# battery_and_current_sense.net
KiCad netlist of a schematic drawn in Altium Designer
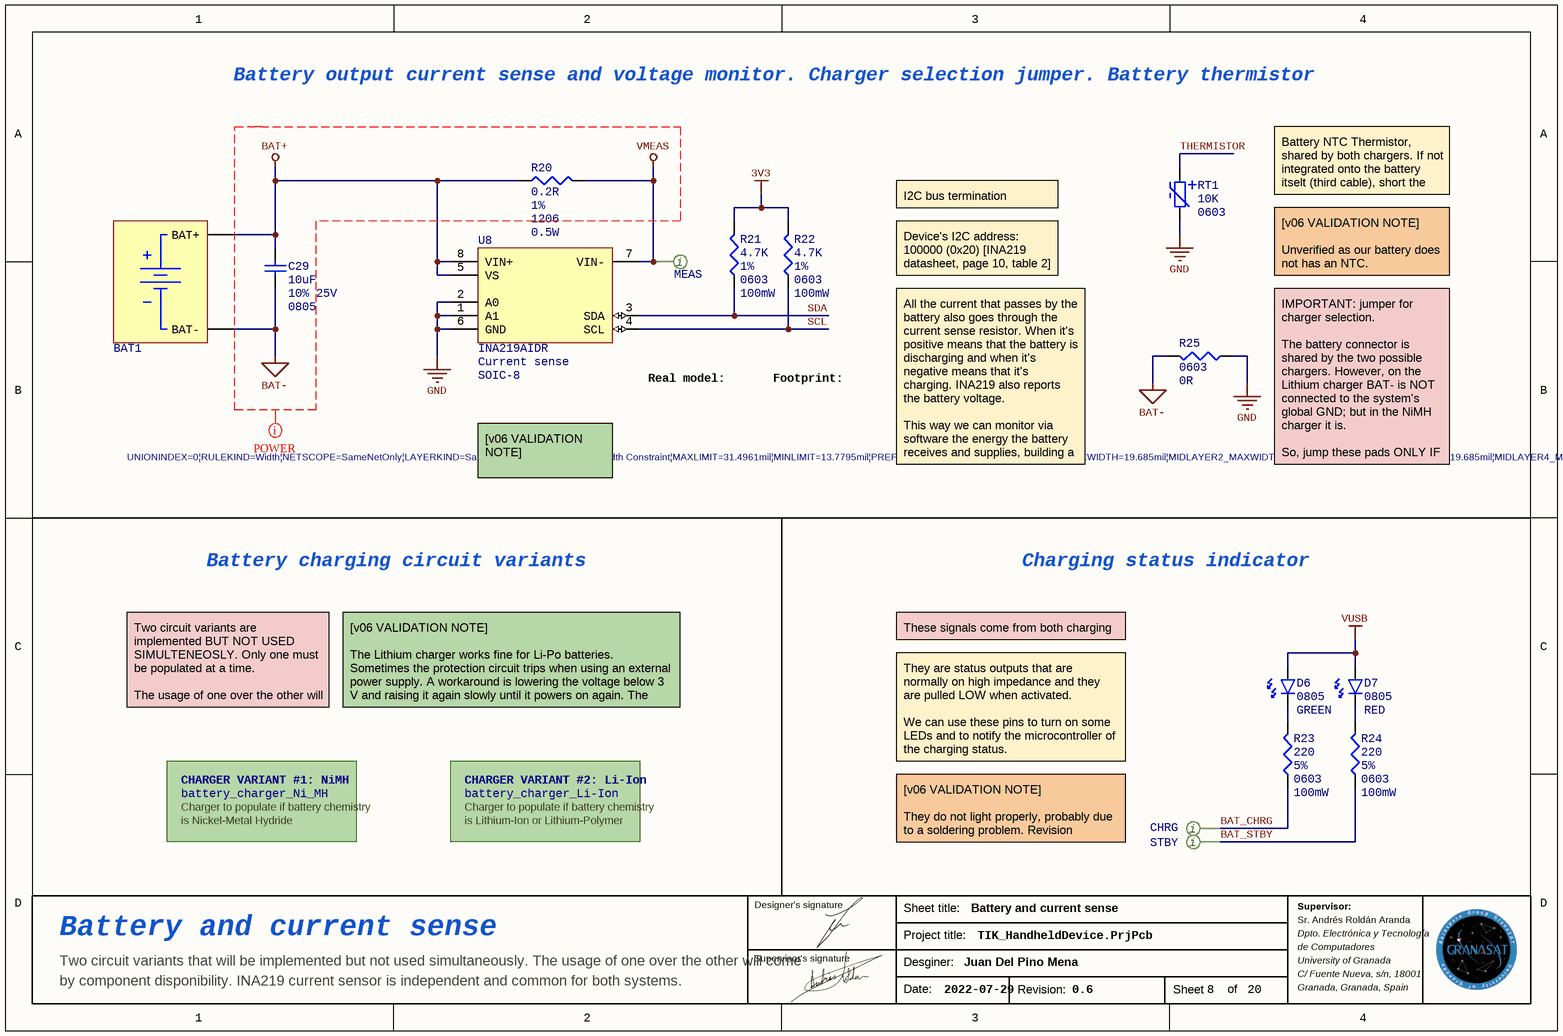
[diagram p0: battery_and_current_sense.SchDoc]

(export (version "E")
  (design (tool "Eeschema 10.0.6"))
  (components
    (comp (ref "BAT1")
      (value "Battery pads")
      (footprint "BATTERY_PADS")
      (description "Generic 2-Pad battery connector")
      (libsource (lib "tik_handheld_schlib") (part "Battery pads"))
    )
    (comp (ref "C29")
      (value "10uF")
      (footprint "CAP 0805_2012")
      (description "Ceramic cap size 0805")
      (fields
        (field (name "TOLERANCE") "10% 25V")
        (field (name "PACKAGEDESCRIPTION") "0805")
        (field (name "Comment") "Cap_cer_0805")
      )
      (libsource (lib "tik_handheld_schlib") (part "Cap_cer_0805_10uF_10%"))
    )
    (comp (ref "CHRG")
      (value "Test Point Pad dual sided")
      (footprint "TEST POINT PAD")
      (description "Test point - PCB Pad dual sided")
      (libsource (lib "tik_handheld_schlib") (part "Test Point Pad dual sided"))
    )
    (comp (ref "D6")
      (value "Diode LED_G_0805")
      (footprint "LED 0805_2012 GREEN")
      (description "Low power LED color Green")
      (fields (field (name "PACKAGEDESCRIPTION") "0805") (field (name "TYPE") "GREEN"))
      (libsource (lib "tik_handheld_schlib") (part "Diode LED_G_0805"))
    )
    (comp (ref "D7")
      (value "Diode LED_R_0805")
      (footprint "LED 0805_2012 RED")
      (description "Low power LED color Red")
      (fields (field (name "PACKAGEDESCRIPTION") "0805") (field (name "TYPE") "RED"))
      (libsource (lib "tik_handheld_schlib") (part "Diode LED_R_0805"))
    )
    (comp (ref "MEAS")
      (value "Test Point Pad dual sided")
      (footprint "TEST POINT PAD")
      (description "Test point - PCB Pad dual sided")
      (libsource (lib "tik_handheld_schlib") (part "Test Point Pad dual sided"))
    )
    (comp (ref "R20")
      (value "0.2R")
      (footprint "RES 1206_3216")
      (description "Res size 1206 SMD mounting, high power, shunt, current sense.")
      (fields
        (field (name "TOLERANCE") "1%")
        (field (name "PACKAGEDESCRIPTION") "1206")
        (field (name "POWERDISIPATED") "0.5W")
        (field (name "Comment") "sense")
      )
      (libsource (lib "tik_handheld_schlib") (part "Res_1206_0R2_1%_500mW"))
    )
    (comp (ref "R21")
      (value "4.7K")
      (footprint "RES 0603_1608")
      (description "Res size 0603 SMD mounting, low power")
      (fields
        (field (name "TOLERANCE") "1%")
        (field (name "PACKAGEDESCRIPTION") "0603")
        (field (name "POWERDISIPATED") "100mW")
        (field (name "Comment") "Res_0603_4.7K_1%_100mW")
      )
      (libsource (lib "tik_handheld_schlib") (part "Res_0603_4.7K_1%_100mW"))
    )
    (comp (ref "R22")
      (value "4.7K")
      (footprint "RES 0603_1608")
      (description "Res size 0603 SMD mounting, low power")
      (fields
        (field (name "TOLERANCE") "1%")
        (field (name "PACKAGEDESCRIPTION") "0603")
        (field (name "POWERDISIPATED") "100mW")
        (field (name "Comment") "Res_0603_4.7K_1%_100mW")
      )
      (libsource (lib "tik_handheld_schlib") (part "Res_0603_4.7K_1%_100mW"))
    )
    (comp (ref "R23")
      (value "220")
      (footprint "RES 0603_1608")
      (description "Res size 0603 SMD mounting, low power")
      (fields
        (field (name "TOLERANCE") "5%")
        (field (name "PACKAGEDESCRIPTION") "0603")
        (field (name "POWERDISIPATED") "100mW")
        (field (name "Comment") "Res_0603_220_5%_100mW")
      )
      (libsource (lib "tik_handheld_schlib") (part "Res_0603_220_5%_100mW"))
    )
    (comp (ref "R24")
      (value "220")
      (footprint "RES 0603_1608")
      (description "Res size 0603 SMD mounting, low power")
      (fields
        (field (name "TOLERANCE") "5%")
        (field (name "PACKAGEDESCRIPTION") "0603")
        (field (name "POWERDISIPATED") "100mW")
        (field (name "Comment") "Res_0603_220_5%_100mW")
      )
      (libsource (lib "tik_handheld_schlib") (part "Res_0603_220_5%_100mW"))
    )
    (comp (ref "R25")
      (value "0R")
      (footprint "RES 0603_1608")
      (description "Res size 0603 SMD mounting, zero-ohm 0R Yageo RC0603JR-070RL")
      (fields
        (field (name "TOLERANCE") "5%")
        (field (name "PACKAGEDESCRIPTION") "0603")
        (field (name "Comment") "Res_0603_0ohm")
      )
      (libsource (lib "tik_handheld_schlib") (part "Res_0603_0ohm"))
    )
    (comp (ref "RT1")
      (value "10K")
      (footprint "NTC THT ver")
      (description "NTC THERMISTOR 10K for solding a cable from the battery NTC")
      (fields (field (name "PACKAGEDESCRIPTION") "0603") (field (name "Comment") "NTC 10K tht"))
      (libsource (lib "tik_handheld_schlib") (part "NTC 10K tht"))
    )
    (comp (ref "STBY")
      (value "Test Point Pad dual sided")
      (footprint "TEST POINT PAD")
      (description "Test point - PCB Pad dual sided")
      (libsource (lib "tik_handheld_schlib") (part "Test Point Pad dual sided"))
    )
    (comp (ref "U8")
      (value "INA219")
      (footprint "SOIC-8-D0008A INA219D")
      (description "Zero-Drift, Bi-Directional CURRENT/POWER MONITOR with I2C. SOIC-8 (D) Package")
      (fields
        (field (name "PART") "INA219AIDR")
        (field (name "TYPE") "Current sense")
        (field (name "PACKAGEDESCRIPTION") "SOIC-8")
      )
      (libsource (lib "tik_handheld_schlib") (part "IC INA219 current sense"))
    )
  )
  (nets
    (net (code "1") (name "/BAT_CHRG") (class "Default")
      (node (ref "CHRG") (pin "1") (pinfunction "1_1") (pintype "passive"))
      (node (ref "R23") (pin "1") (pinfunction "1_1") (pintype "passive"))
    )
    (net (code "2") (name "/BAT_STBY") (class "Default")
      (node (ref "R24") (pin "1") (pinfunction "1_1") (pintype "passive"))
      (node (ref "STBY") (pin "1") (pinfunction "1_1") (pintype "passive"))
    )
    (net (code "3") (name "/SCL") (class "Default")
      (node (ref "R22") (pin "1") (pinfunction "1_1") (pintype "passive"))
      (node (ref "U8") (pin "4") (pinfunction "SCL_4") (pintype "bidirectional"))
    )
    (net (code "4") (name "/SDA") (class "Default")
      (node (ref "R21") (pin "1") (pinfunction "1_1") (pintype "passive"))
      (node (ref "U8") (pin "3") (pinfunction "SDA_3") (pintype "bidirectional"))
    )
    (net (code "5") (name "/THERMISTOR") (class "Default")
      (node (ref "RT1") (pin "1") (pinfunction "1_1") (pintype "passive"))
    )
    (net (code "6") (name "3V3") (class "Default")
      (node (ref "R21") (pin "2") (pinfunction "2_2") (pintype "passive"))
      (node (ref "R22") (pin "2") (pinfunction "2_2") (pintype "passive"))
    )
    (net (code "7") (name "BAT+") (class "Default")
      (node (ref "BAT1") (pin "2") (pinfunction "BAT+_2") (pintype "passive"))
      (node (ref "C29") (pin "2") (pinfunction "2_2") (pintype "passive"))
      (node (ref "R20") (pin "1") (pinfunction "1_1") (pintype "passive"))
      (node (ref "U8") (pin "5") (pinfunction "VS_5") (pintype "power_in"))
      (node (ref "U8") (pin "8") (pinfunction "VIN+_8") (pintype "passive"))
    )
    (net (code "8") (name "BAT-") (class "Default")
      (node (ref "BAT1") (pin "1") (pinfunction "BAT-_1") (pintype "passive"))
      (node (ref "C29") (pin "1") (pinfunction "1_1") (pintype "passive"))
      (node (ref "R25") (pin "2") (pinfunction "2_2") (pintype "passive"))
    )
    (net (code "9") (name "GND") (class "Default")
      (node (ref "R25") (pin "1") (pinfunction "1_1") (pintype "passive"))
      (node (ref "RT1") (pin "2") (pinfunction "2_2") (pintype "passive"))
      (node (ref "U8") (pin "1") (pinfunction "A1_1") (pintype "passive"))
      (node (ref "U8") (pin "2") (pinfunction "A0_2") (pintype "passive"))
      (node (ref "U8") (pin "6") (pinfunction "GND_6") (pintype "power_in"))
    )
    (net (code "10") (name "Net-(D6-Pad2)") (class "Default")
      (node (ref "D6") (pin "2") (pinfunction "2_2") (pintype "passive"))
      (node (ref "R23") (pin "2") (pinfunction "2_2") (pintype "passive"))
    )
    (net (code "11") (name "Net-(D7-Pad2)") (class "Default")
      (node (ref "D7") (pin "2") (pinfunction "2_2") (pintype "passive"))
      (node (ref "R24") (pin "2") (pinfunction "2_2") (pintype "passive"))
    )
    (net (code "12") (name "VMEAS") (class "Default")
      (node (ref "MEAS") (pin "1") (pinfunction "1_1") (pintype "passive"))
      (node (ref "R20") (pin "2") (pinfunction "2_2") (pintype "passive"))
      (node (ref "U8") (pin "7") (pinfunction "VIN-_7") (pintype "passive"))
    )
    (net (code "13") (name "VUSB") (class "Default")
      (node (ref "D6") (pin "1") (pinfunction "1_1") (pintype "passive"))
      (node (ref "D7") (pin "1") (pinfunction "1_1") (pintype "passive"))
    )
  )
)
